# Power_Supply_Motor.net
KiCad netlist of a schematic drawn in Altium Designer
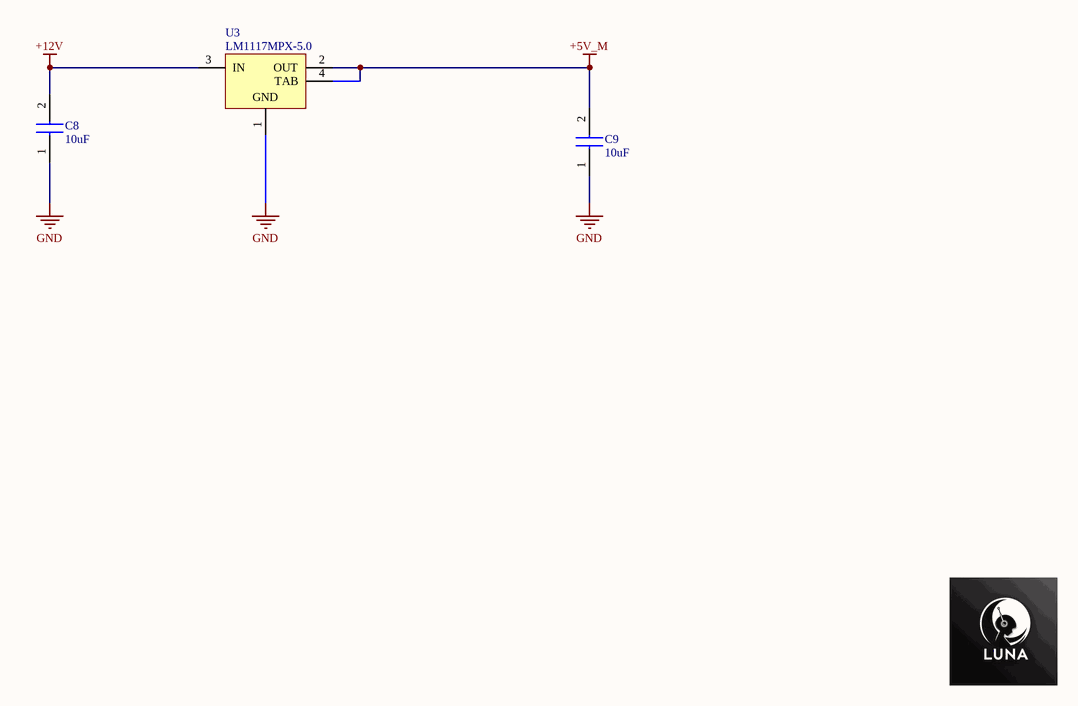
[diagram p0: Power_Supply_Motor.SchDoc]

(export (version "E")
  (design (tool "Eeschema 10.0.6"))
  (components
    (comp (ref "C8")
      (value "10uF")
      (footprint "SamacSys:CAPC1608X90N")
      (description "CL10A106KP8NNNC Capacitor")
      (fields
        (field (name "MANUFACTURER_PART_NUMBER") "CL10A106KP8NNNC")
        (field (name "MOUSER PART NUMBER") "187-CL10A106KP8NNNC")
      )
      (libsource (lib "*") (part "CL10A106KP8NNNC"))
    )
    (comp (ref "C9")
      (value "10uF")
      (footprint "SamacSys:CAPC1608X90N")
      (description "CL10A106KP8NNNC Capacitor")
      (fields
        (field (name "MANUFACTURER_PART_NUMBER") "CL10A106KP8NNNC")
        (field (name "MOUSER PART NUMBER") "187-CL10A106KP8NNNC")
      )
      (libsource (lib "*") (part "CL10A106KP8NNNC"))
    )
    (comp (ref "U3")
      (value "LM1117MPX-5.0")
      (footprint "DCY0004A_L")
      (description "800mA Low-Dropout Linear Regulator, 4-pin SOT-223")
      (fields (field (name "MANUFACTURER") "Texas Instruments"))
      (libsource (lib "Altium Content Vault") (part "PM-REG-LM1086-SOT4"))
    )
  )
  (nets
    (net (code "1") (name "+5V_M") (class "Default")
      (node (ref "C9") (pin "2") (pinfunction "2_2") (pintype "passive"))
      (node (ref "U3") (pin "2") (pinfunction "OUT_2") (pintype "power_in"))
      (node (ref "U3") (pin "4") (pinfunction "TAB_4") (pintype "power_in"))
    )
    (net (code "2") (name "+12V") (class "Default")
      (node (ref "C8") (pin "2") (pinfunction "2_2") (pintype "passive"))
      (node (ref "U3") (pin "3") (pinfunction "IN_3") (pintype "power_in"))
    )
    (net (code "3") (name "GND") (class "Default")
      (node (ref "C8") (pin "1") (pinfunction "1_1") (pintype "passive"))
      (node (ref "C9") (pin "1") (pinfunction "1_1") (pintype "passive"))
      (node (ref "U3") (pin "1") (pinfunction "GND_1") (pintype "power_in"))
    )
  )
)
